# PowerSupply.net
KiCad netlist of a schematic drawn in Altium Designer
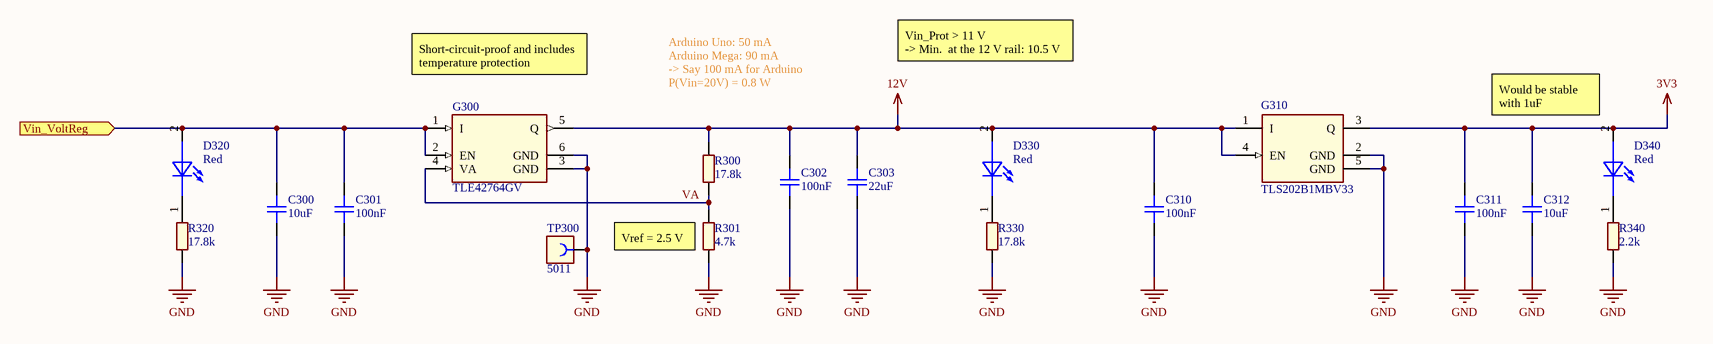
[diagram p0: PowerSupply.SchDoc]

(export (version "E")
  (design (tool "Eeschema 10.0.6"))
  (components
    (comp (ref "C300")
      (value "10uF")
      (footprint "CAPC3216X190N-1")
      (description "CAP / CERA / 10uF / 50V / 20% / X5R (EIA) / -55°C to 85°C / 1206 (3216) / SMD / -")
      (fields (field (name "MANUFACTURER") "Taiyo Yuden"))
      (libsource (lib "PCBLibraryData") (part "CAP-SGL-STD-02P_00000001"))
    )
    (comp (ref "C301")
      (value "100nF")
      (footprint "CAPC1608X90N-2")
      (description "CAP / CERA / 100nF / 50V / 10% / X7R (EIA) / -55°C to 125°C / 0603 / SMD / -")
      (fields (field (name "MANUFACTURER") "AVX"))
      (libsource (lib "PCBLibraryData") (part "CAP-SGL-STD-02P_00000001"))
    )
    (comp (ref "C302")
      (value "100nF")
      (footprint "CAPC1608X90N-2")
      (description "CAP / CERA / 100nF / 50V / 10% / X7R (EIA) / -55°C to 125°C / 0603 / SMD / -")
      (fields (field (name "MANUFACTURER") "AVX"))
      (libsource (lib "PCBLibraryData") (part "CAP-SGL-STD-02P_00000001"))
    )
    (comp (ref "C303")
      (value "22uF")
      (footprint "CAPC3225X270N-0")
      (description "CAP / CERA / 22uF / 25V / 10% / X5R (EIA) / -55°C to 85°C / 1210(3225) / SMD / -")
      (fields (field (name "MANUFACTURER") "Taiyo Yuden"))
      (libsource (lib "PCBLibraryData") (part "CAP-SGL-STD-02P_00000001"))
    )
    (comp (ref "C310")
      (value "100nF")
      (footprint "CAPC1608X90N-2")
      (description "CAP / CERA / 100nF / 50V / 10% / X7R (EIA) / -55°C to 125°C / 0603 / SMD / -")
      (fields (field (name "MANUFACTURER") "AVX"))
      (libsource (lib "PCBLibraryData") (part "CAP-SGL-STD-02P_00000001"))
    )
    (comp (ref "C311")
      (value "100nF")
      (footprint "CAPC1608X90N-2")
      (description "CAP / CERA / 100nF / 50V / 10% / X7R (EIA) / -55°C to 125°C / 0603 / SMD / -")
      (fields (field (name "MANUFACTURER") "AVX"))
      (libsource (lib "PCBLibraryData") (part "CAP-SGL-STD-02P_00000001"))
    )
    (comp (ref "C312")
      (value "10uF")
      (footprint "CAPC3216X190N-1")
      (description "CAP / CERA / 10uF / 50V / 20% / X5R (EIA) / -55°C to 85°C / 1206 (3216) / SMD / -")
      (fields (field (name "MANUFACTURER") "Taiyo Yuden"))
      (libsource (lib "PCBLibraryData") (part "CAP-SGL-STD-02P_00000001"))
    )
    (comp (ref "D320")
      (value "Red")
      (footprint "LEDSC160X80X80-2N-1")
      (description "WL-SMCW SMT Mono-color Chip LED Waterclear, Red,630nm")
      (fields (field (name "MANUFACTURER") "Wurth Elektronik"))
      (libsource (lib "PCBLibraryData") (part "d_led_a"))
    )
    (comp (ref "D330")
      (value "Red")
      (footprint "LEDSC160X80X80-2N-1")
      (description "WL-SMCW SMT Mono-color Chip LED Waterclear, Red,630nm")
      (fields (field (name "MANUFACTURER") "Wurth Elektronik"))
      (libsource (lib "PCBLibraryData") (part "d_led_a"))
    )
    (comp (ref "D340")
      (value "Red")
      (footprint "LEDSC160X80X80-2N-1")
      (description "WL-SMCW SMT Mono-color Chip LED Waterclear, Red,630nm")
      (fields (field (name "MANUFACTURER") "Wurth Elektronik"))
      (libsource (lib "PCBLibraryData") (part "d_led_a"))
    )
    (comp (ref "G300")
      (value "TLE42764GV")
      (footprint "TO170P1500X450-6N-V")
      (description "Monolithic integrated low dropout voltage regulator")
      (fields (field (name "MANUFACTURER") "Infineon Technologies"))
      (libsource (lib "PCBLibraryData") (part "TLE42764GV"))
    )
    (comp (ref "G310")
      (value "TLS202B1MBV33")
      (footprint "PG-SCT595")
      (description "Fixed Linear Voltage Post Regulator, 3.3V")
      (fields
        (field (name "LEGACY PARTNUMBER") "IFX01401269")
        (field (name "MANUFACTURER") "Infineon Technologies")
      )
      (libsource (lib "PCBLibraryData") (part "TLS202B1MBV33"))
    )
    (comp (ref "R300")
      (value "17.8k")
      (footprint "RESC1609X50N")
      (description "RES / STD / 17.8k / 100mW / 1% / 100ppm/K / -55°C to 155°C / 0603 / SMD / -")
      (fields (field (name "LEGACY PARTNUMBER") "RES01801283") (field (name "MANUFACTURER") "Vishay"))
      (libsource (lib "PCBLibraryData") (part "RES-SGL-STD-02P_00000006"))
    )
    (comp (ref "R301")
      (value "4.7k")
      (footprint "RESC1609X50N")
      (description "RES / STD / 4.7k / 100mW / 1% / 100ppm/K / -55°C to 155°C / 0603 / SMD / -")
      (fields (field (name "LEGACY PARTNUMBER") "RES01801219") (field (name "MANUFACTURER") "Vishay"))
      (libsource (lib "PCBLibraryData") (part "RES-SGL-STD-02P_00000006"))
    )
    (comp (ref "R320")
      (value "17.8k")
      (footprint "RESC1609X50N")
      (description "RES / STD / 17.8k / 100mW / 1% / 100ppm/K / -55°C to 155°C / 0603 / SMD / -")
      (fields (field (name "LEGACY PARTNUMBER") "RES01801283") (field (name "MANUFACTURER") "Vishay"))
      (libsource (lib "PCBLibraryData") (part "RES-SGL-STD-02P_00000006"))
    )
    (comp (ref "R330")
      (value "17.8k")
      (footprint "RESC1609X50N")
      (description "RES / STD / 17.8k / 100mW / 1% / 100ppm/K / -55°C to 155°C / 0603 / SMD / -")
      (fields (field (name "LEGACY PARTNUMBER") "RES01801283") (field (name "MANUFACTURER") "Vishay"))
      (libsource (lib "PCBLibraryData") (part "RES-SGL-STD-02P_00000006"))
    )
    (comp (ref "R340")
      (value "2.2k")
      (footprint "RESC1609X50N")
      (description "RES / STD / 2.2k / 100mW / 1% / 100ppm/K / -55°C to 155°C / 0603 / SMD / -")
      (fields (field (name "LEGACY PARTNUMBER") "RES01801179") (field (name "MANUFACTURER") "Vishay"))
      (libsource (lib "PCBLibraryData") (part "RES-SGL-STD-02P_00000006"))
    )
    (comp (ref "TP300")
      (value "5011")
      (footprint "CON-THT-TP-5011")
      (description "PC Test Point-Multipurpose THT, Black")
      (fields
        (field (name "LEGACY PARTNUMBER") "CON01500530")
        (field (name "MANUFACTURER") "Keystone Electronics Corp.")
      )
      (libsource (lib "PCBLibraryData") (part "connector_1_f"))
    )
  )
  (nets
    (net (code "1") (name "/VA") (class "Default")
      (node (ref "G300") (pin "4") (pinfunction "VA_4") (pintype "input"))
      (node (ref "R300") (pin "1") (pinfunction "1_1") (pintype "passive"))
      (node (ref "R301") (pin "2") (pinfunction "2_2") (pintype "passive"))
    )
    (net (code "2") (name "/Vin_VoltReg") (class "Default")
      (node (ref "C300") (pin "2") (pinfunction "2_2") (pintype "passive"))
      (node (ref "C301") (pin "2") (pinfunction "2_2") (pintype "passive"))
      (node (ref "D320") (pin "2") (pinfunction "Anode_2") (pintype "passive"))
      (node (ref "G300") (pin "1") (pinfunction "I_1") (pintype "input"))
      (node (ref "G300") (pin "2") (pinfunction "EN_2") (pintype "input"))
    )
    (net (code "3") (name "3V3") (class "Default")
      (node (ref "C311") (pin "2") (pinfunction "2_2") (pintype "passive"))
      (node (ref "C312") (pin "2") (pinfunction "2_2") (pintype "passive"))
      (node (ref "D340") (pin "2") (pinfunction "Anode_2") (pintype "passive"))
      (node (ref "G310") (pin "3") (pinfunction "Q_3") (pintype "power_in"))
    )
    (net (code "4") (name "12V") (class "Default")
      (node (ref "C302") (pin "2") (pinfunction "2_2") (pintype "passive"))
      (node (ref "C303") (pin "2") (pinfunction "2_2") (pintype "passive"))
      (node (ref "C310") (pin "2") (pinfunction "2_2") (pintype "passive"))
      (node (ref "D330") (pin "2") (pinfunction "Anode_2") (pintype "passive"))
      (node (ref "G300") (pin "5") (pinfunction "Q_5") (pintype "output"))
      (node (ref "G310") (pin "1") (pinfunction "I_1") (pintype "power_in"))
      (node (ref "G310") (pin "4") (pinfunction "EN_4") (pintype "input"))
      (node (ref "R300") (pin "2") (pinfunction "2_2") (pintype "passive"))
    )
    (net (code "5") (name "GND") (class "Default")
      (node (ref "C300") (pin "1") (pinfunction "1_1") (pintype "passive"))
      (node (ref "C301") (pin "1") (pinfunction "1_1") (pintype "passive"))
      (node (ref "C302") (pin "1") (pinfunction "1_1") (pintype "passive"))
      (node (ref "C303") (pin "1") (pinfunction "1_1") (pintype "passive"))
      (node (ref "C310") (pin "1") (pinfunction "1_1") (pintype "passive"))
      (node (ref "C311") (pin "1") (pinfunction "1_1") (pintype "passive"))
      (node (ref "C312") (pin "1") (pinfunction "1_1") (pintype "passive"))
      (node (ref "G300") (pin "3") (pinfunction "GND_3") (pintype "power_in"))
      (node (ref "G300") (pin "6") (pinfunction "GND_6") (pintype "power_in"))
      (node (ref "G310") (pin "2") (pinfunction "GND_2") (pintype "power_in"))
      (node (ref "G310") (pin "5") (pinfunction "GND_5") (pintype "power_in"))
      (node (ref "R301") (pin "1") (pinfunction "1_1") (pintype "passive"))
      (node (ref "R320") (pin "1") (pinfunction "1_1") (pintype "passive"))
      (node (ref "R330") (pin "1") (pinfunction "1_1") (pintype "passive"))
      (node (ref "R340") (pin "1") (pinfunction "1_1") (pintype "passive"))
      (node (ref "TP300") (pin "1") (pinfunction "1_1") (pintype "passive"))
    )
    (net (code "6") (name "Net-(D320-Cathode)") (class "Default")
      (node (ref "D320") (pin "1") (pinfunction "Cathode_1") (pintype "passive"))
      (node (ref "R320") (pin "2") (pinfunction "2_2") (pintype "passive"))
    )
    (net (code "7") (name "Net-(D330-Cathode)") (class "Default")
      (node (ref "D330") (pin "1") (pinfunction "Cathode_1") (pintype "passive"))
      (node (ref "R330") (pin "2") (pinfunction "2_2") (pintype "passive"))
    )
    (net (code "8") (name "Net-(D340-Cathode)") (class "Default")
      (node (ref "D340") (pin "1") (pinfunction "Cathode_1") (pintype "passive"))
      (node (ref "R340") (pin "2") (pinfunction "2_2") (pintype "passive"))
    )
  )
)
